# KMO_IO_MV7.net
KiCad netlist of a schematic drawn in EAGLE
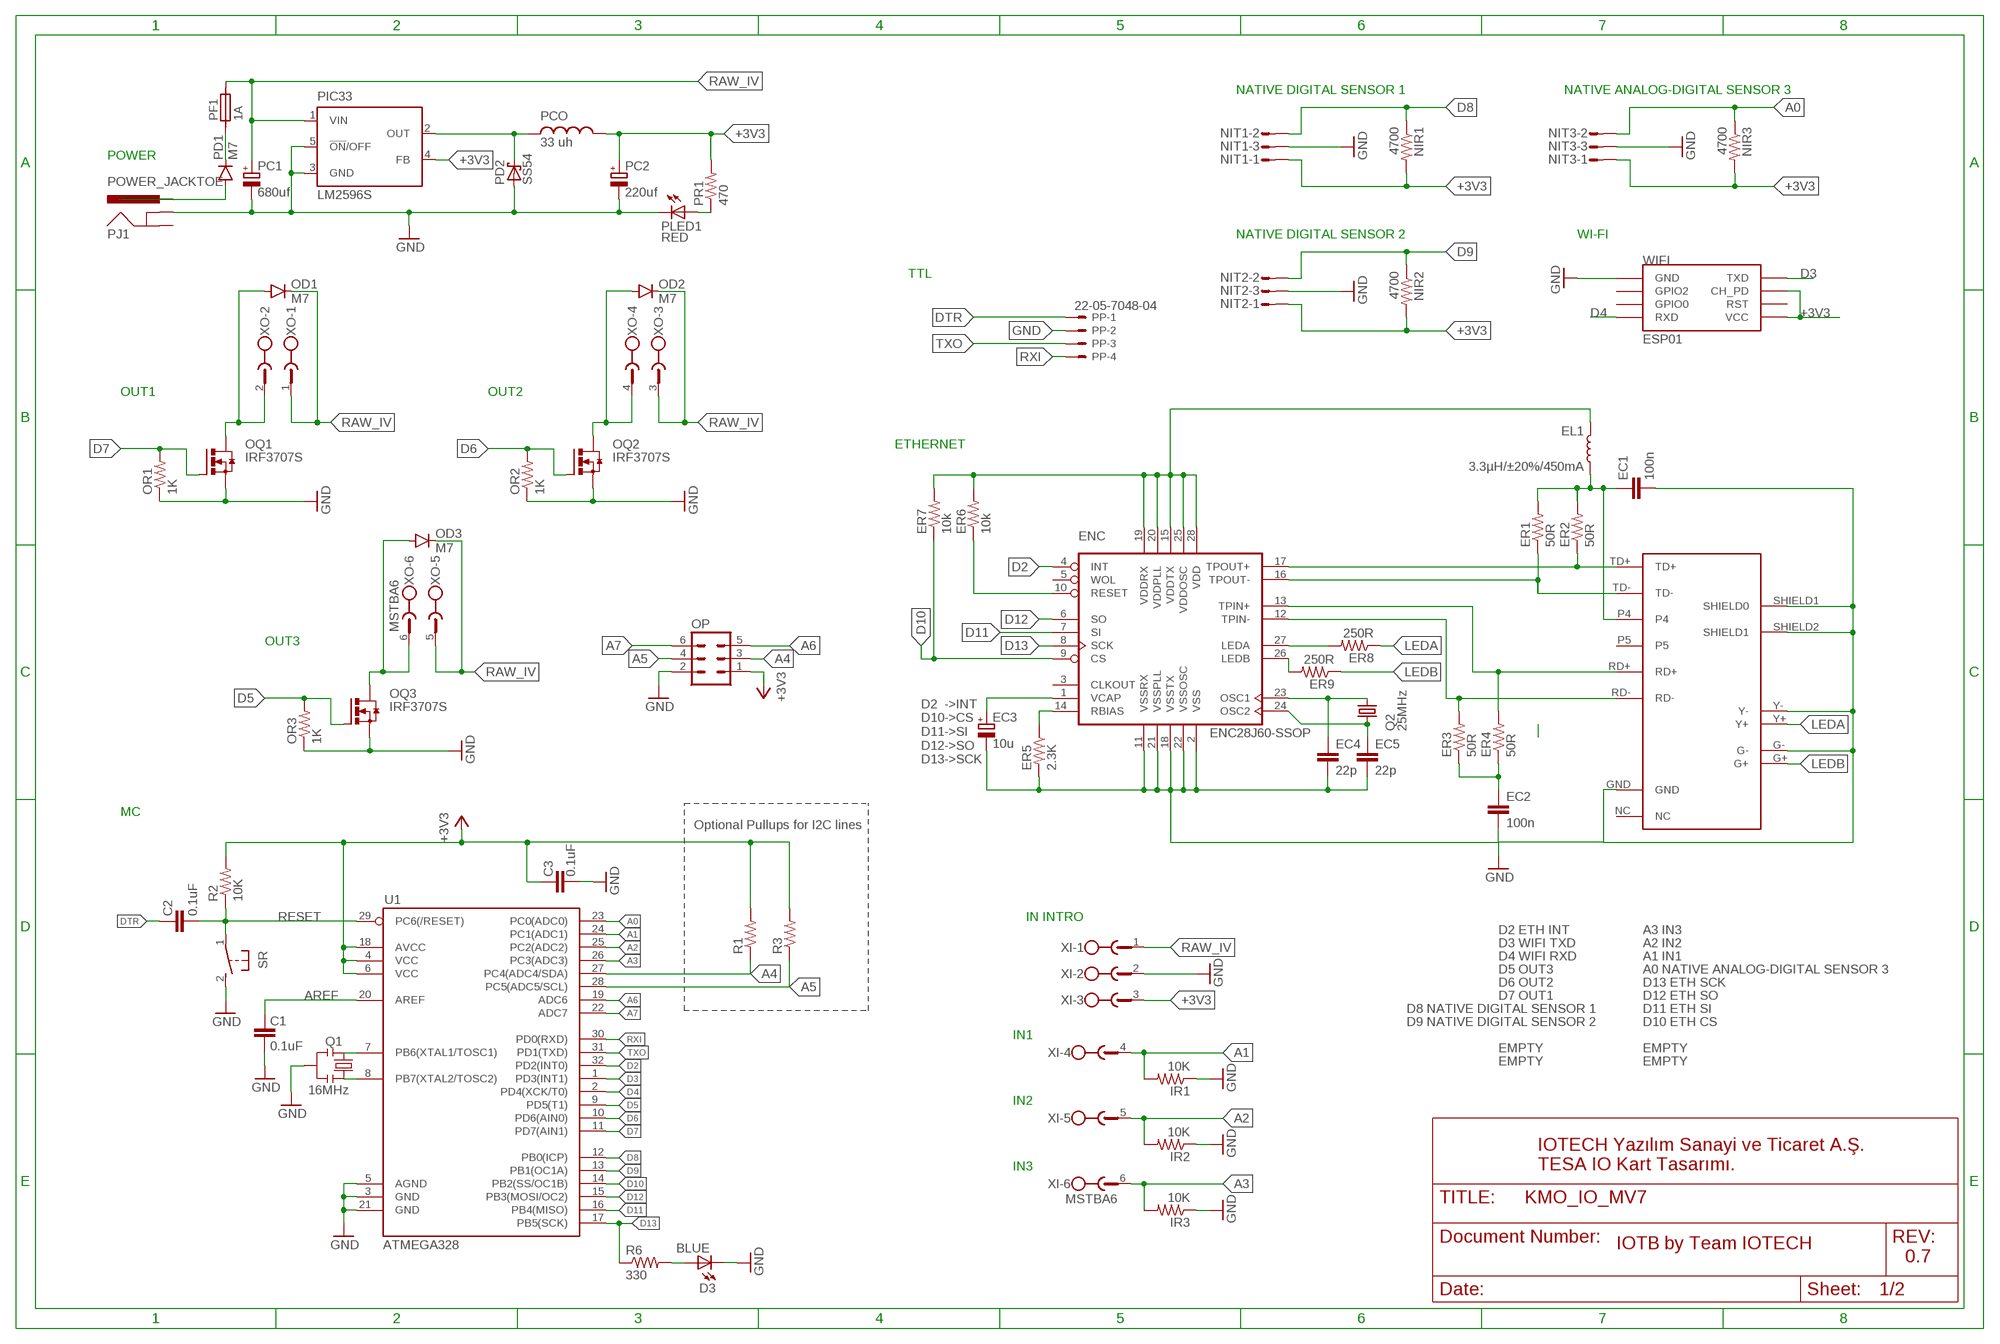
[diagram p0: schematic, sheet 1]
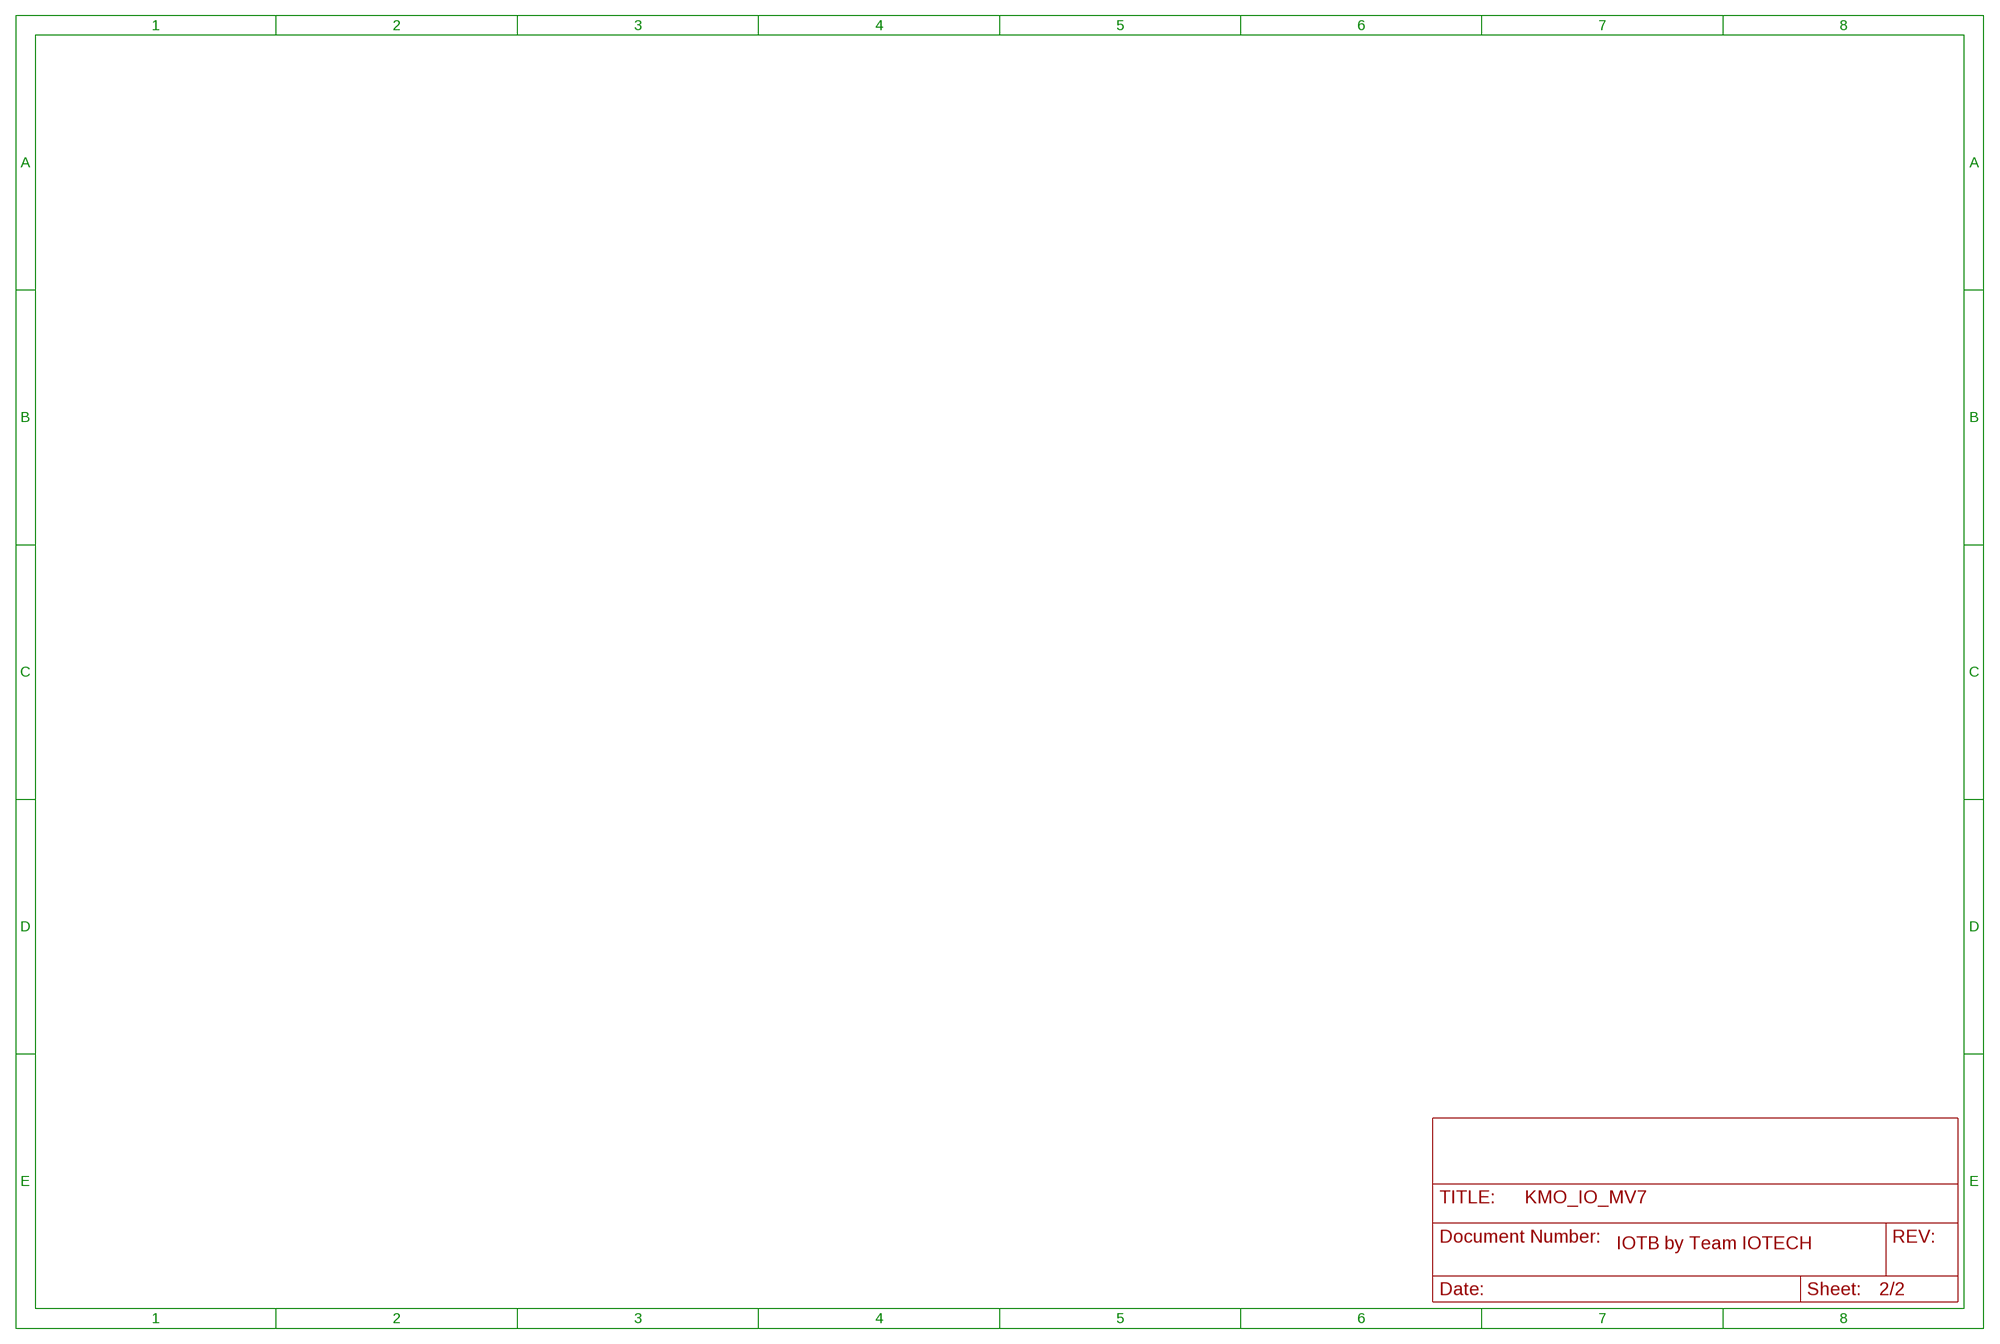
[diagram p1: schematic, sheet 2]

(export (version "E")
  (design (tool "Eeschema 10.0.6"))
  (components
    (comp (ref "C1")
      (value "0.1uF")
      (footprint "eagle-import:0805")
      (libsource (lib "eagle-import") (part "CAP0805"))
    )
    (comp (ref "C2")
      (value "0.1uF")
      (footprint "eagle-import:0805")
      (libsource (lib "eagle-import") (part "CAP0805"))
    )
    (comp (ref "C3")
      (value "0.1uF")
      (footprint "eagle-import:0805")
      (libsource (lib "eagle-import") (part "CAP0805"))
    )
    (comp (ref "D3")
      (value "BLUE")
      (footprint "eagle-import:CHIP-LED0805")
      (libsource (lib "eagle-import") (part "LEDCHIP-LED0805"))
    )
    (comp (ref "EC1")
      (value "100n")
      (footprint "eagle-import:0805")
      (libsource (lib "eagle-import") (part "CAP0805"))
    )
    (comp (ref "EC2")
      (value "100n")
      (footprint "eagle-import:0805")
      (libsource (lib "eagle-import") (part "CAP0805"))
    )
    (comp (ref "EC3")
      (value "10u")
      (footprint "eagle-import:CT3216")
      (libsource (lib "eagle-import") (part "CPOL-EUCT3216"))
    )
    (comp (ref "EC4")
      (value "22p")
      (footprint "eagle-import:0805")
      (libsource (lib "eagle-import") (part "CAP0805"))
    )
    (comp (ref "EC5")
      (value "22p")
      (footprint "eagle-import:0805")
      (libsource (lib "eagle-import") (part "CAP0805"))
    )
    (comp (ref "EL1")
      (value "3.3µH/±20%/450mA")
      (footprint "eagle-import:0805")
      (libsource (lib "eagle-import") (part "INDUCTOR-0805-3.3UH"))
    )
    (comp (ref "ENC")
      (value "ENC28J60-SSOP")
      (footprint "eagle-import:SSOP28")
      (libsource (lib "eagle-import") (part "ENC28J60-SSOP"))
    )
    (comp (ref "ER1")
      (value "50R")
      (footprint "eagle-import:0805")
      (libsource (lib "eagle-import") (part "RESISTOR0805-RES"))
    )
    (comp (ref "ER2")
      (value "50R")
      (footprint "eagle-import:0805")
      (libsource (lib "eagle-import") (part "RESISTOR0805-RES"))
    )
    (comp (ref "ER3")
      (value "50R")
      (footprint "eagle-import:0805")
      (libsource (lib "eagle-import") (part "RESISTOR0805-RES"))
    )
    (comp (ref "ER4")
      (value "50R")
      (footprint "eagle-import:0805")
      (libsource (lib "eagle-import") (part "RESISTOR0805-RES"))
    )
    (comp (ref "ER5")
      (value "2.3K")
      (footprint "eagle-import:0805")
      (libsource (lib "eagle-import") (part "RESISTOR0805-RES"))
    )
    (comp (ref "ER6")
      (value "10k")
      (footprint "eagle-import:0805")
      (libsource (lib "eagle-import") (part "RESISTOR0805-RES"))
    )
    (comp (ref "ER7")
      (value "10k")
      (footprint "eagle-import:0805")
      (libsource (lib "eagle-import") (part "RESISTOR0805-RES"))
    )
    (comp (ref "ER8")
      (value "250R")
      (footprint "eagle-import:0805")
      (libsource (lib "eagle-import") (part "RESISTOR0805-RES"))
    )
    (comp (ref "ER9")
      (value "250R")
      (footprint "eagle-import:0805")
      (libsource (lib "eagle-import") (part "RESISTOR0805-RES"))
    )
    (comp (ref "IR1")
      (value "10K")
      (footprint "eagle-import:0805")
      (libsource (lib "eagle-import") (part "RESISTOR0805-RES"))
    )
    (comp (ref "IR2")
      (value "10K")
      (footprint "eagle-import:0805")
      (libsource (lib "eagle-import") (part "RESISTOR0805-RES"))
    )
    (comp (ref "IR3")
      (value "10K")
      (footprint "eagle-import:0805")
      (libsource (lib "eagle-import") (part "RESISTOR0805-RES"))
    )
    (comp (ref "NIR1")
      (value "4700")
      (footprint "eagle-import:0805")
      (libsource (lib "eagle-import") (part "RESISTOR0805-RES"))
    )
    (comp (ref "NIR2")
      (value "4700")
      (footprint "eagle-import:0805")
      (libsource (lib "eagle-import") (part "RESISTOR0805-RES"))
    )
    (comp (ref "NIR3")
      (value "4700")
      (footprint "eagle-import:0805")
      (libsource (lib "eagle-import") (part "RESISTOR0805-RES"))
    )
    (comp (ref "NIT1")
      (value "S03P")
      (footprint "eagle-import:S03P")
      (libsource (lib "eagle-import") (part "S03P"))
    )
    (comp (ref "NIT2")
      (value "S03P")
      (footprint "eagle-import:S03P")
      (libsource (lib "eagle-import") (part "S03P"))
    )
    (comp (ref "NIT3")
      (value "S03P")
      (footprint "eagle-import:S03P")
      (libsource (lib "eagle-import") (part "S03P"))
    )
    (comp (ref "OD1")
      (value "M7")
      (footprint "eagle-import:SMA-DIODE")
      (libsource (lib "eagle-import") (part "DIODESMA"))
    )
    (comp (ref "OD2")
      (value "M7")
      (footprint "eagle-import:SMA-DIODE")
      (libsource (lib "eagle-import") (part "DIODESMA"))
    )
    (comp (ref "OD3")
      (value "M7")
      (footprint "eagle-import:SMA-DIODE")
      (libsource (lib "eagle-import") (part "DIODESMA"))
    )
    (comp (ref "OP")
      (value "MA03-2")
      (footprint "eagle-import:MA03-2")
      (libsource (lib "eagle-import") (part "MA03-2"))
    )
    (comp (ref "OQ1")
      (value "IRF3707S")
      (footprint "eagle-import:D2PACK")
      (libsource (lib "eagle-import") (part "IRF3704S"))
    )
    (comp (ref "OQ2")
      (value "IRF3707S")
      (footprint "eagle-import:D2PACK")
      (libsource (lib "eagle-import") (part "IRF3704S"))
    )
    (comp (ref "OQ3")
      (value "IRF3707S")
      (footprint "eagle-import:D2PACK")
      (libsource (lib "eagle-import") (part "IRF3704S"))
    )
    (comp (ref "OR1")
      (value "1K")
      (footprint "eagle-import:0805")
      (libsource (lib "eagle-import") (part "RESISTOR0805-RES"))
    )
    (comp (ref "OR2")
      (value "1K")
      (footprint "eagle-import:0805")
      (libsource (lib "eagle-import") (part "RESISTOR0805-RES"))
    )
    (comp (ref "OR3")
      (value "1K")
      (footprint "eagle-import:0805")
      (libsource (lib "eagle-import") (part "RESISTOR0805-RES"))
    )
    (comp (ref "PC1")
      (value "680uf")
      (footprint "eagle-import:140CLH-1010")
      (libsource (lib "eagle-import") (part "CPOL-EU140CLH-1010"))
    )
    (comp (ref "PC2")
      (value "220uf")
      (footprint "eagle-import:140CLH-1010")
      (libsource (lib "eagle-import") (part "CPOL-EU140CLH-1010"))
    )
    (comp (ref "PCO")
      (value "33 uh")
      (footprint "eagle-import:MSS1260")
      (libsource (lib "eagle-import") (part "MSS1260"))
    )
    (comp (ref "PD1")
      (value "M7")
      (footprint "eagle-import:SMA-DIODE")
      (libsource (lib "eagle-import") (part "DIODESMA"))
    )
    (comp (ref "PD2")
      (value "SS54")
      (footprint "eagle-import:SMB")
      (libsource (lib "eagle-import") (part "SCHOTTKY-DIODESMD"))
    )
    (comp (ref "PF1")
      (value "1A")
      (footprint "eagle-import:1820")
      (libsource (lib "eagle-import") (part "SIBA194600"))
    )
    (comp (ref "PIC33")
      (value "LM2596S")
      (footprint "eagle-import:TO263-5")
      (fields (field (name "MF") "NATIONAL SEMICONDUCTOR") (field (name "MPN") "LM2596S-ADJ/NOPB"))
      (libsource (lib "eagle-import") (part "LM2596S"))
    )
    (comp (ref "PJ1")
      (value "POWER_JACKTOE")
      (footprint "eagle-import:POWER_JACK_SMD_OVERPASTE_TOE")
      (libsource (lib "eagle-import") (part "POWER_JACKTOE"))
    )
    (comp (ref "PLED1")
      (value "RED")
      (footprint "eagle-import:CHIP-LED0805")
      (libsource (lib "eagle-import") (part "LEDCHIP-LED0805"))
    )
    (comp (ref "PP")
      (value "22-05-7048-04")
      (footprint "eagle-import:7395-04")
      (fields (field (name "MF") "MOLEX"))
      (libsource (lib "eagle-import") (part "22-?-0405-7048"))
    )
    (comp (ref "PR1")
      (value "470")
      (footprint "eagle-import:0805")
      (libsource (lib "eagle-import") (part "RESISTOR0805-RES"))
    )
    (comp (ref "Q1")
      (value "16MHz")
      (footprint "eagle-import:RESONATOR-SMD-1_1")
      (libsource (lib "eagle-import") (part "RESONATOR1{colon}1"))
    )
    (comp (ref "Q2")
      (value "25MHz")
      (footprint "eagle-import:5.0X3.2_2")
      (libsource (lib "eagle-import") (part "KX-9B"))
    )
    (comp (ref "R1")
      (value "RESISTOR0805-RES")
      (footprint "eagle-import:0805")
      (libsource (lib "eagle-import") (part "RESISTOR0805-RES"))
    )
    (comp (ref "R2")
      (value "10K")
      (footprint "eagle-import:0805")
      (libsource (lib "eagle-import") (part "RESISTOR0805-RES"))
    )
    (comp (ref "R3")
      (value "RESISTOR0805-RES")
      (footprint "eagle-import:0805")
      (libsource (lib "eagle-import") (part "RESISTOR0805-RES"))
    )
    (comp (ref "R6")
      (value "330")
      (footprint "eagle-import:0805")
      (libsource (lib "eagle-import") (part "RESISTOR0805-RES"))
    )
    (comp (ref "SR")
      (value "31-XX")
      (footprint "eagle-import:B3F-31XX")
      (fields (field (name "MPN") "B3F-3100"))
      (libsource (lib "eagle-import") (part "31-XX"))
    )
    (comp (ref "U$2")
      (value "HR911105A")
      (footprint "eagle-import:RJ45")
      (libsource (lib "eagle-import") (part "HR911105A"))
    )
    (comp (ref "U1")
      (value "ATMEGA328")
      (footprint "eagle-import:TQFP32-08")
      (libsource (lib "eagle-import") (part "ATMEGA168"))
    )
    (comp (ref "WIFI")
      (value "ESP01")
      (footprint "eagle-import:ESP01")
      (libsource (lib "eagle-import") (part "ESP01"))
    )
    (comp (ref "XI")
      (value "MSTBA6")
      (footprint "eagle-import:MSTBA6")
      (fields (field (name "MF") "FARNELL") (field (name "MPN") "1757284"))
      (libsource (lib "eagle-import") (part "MSTBA6"))
    )
    (comp (ref "XO")
      (value "MSTBA6")
      (footprint "eagle-import:MSTBA6")
      (fields (field (name "MF") "FARNELL") (field (name "MPN") "1757284"))
      (libsource (lib "eagle-import") (part "MSTBA6"))
    )
  )
  (nets
    (net (code "1") (name "+3V3") (class "Default")
      (node (ref "C3") (pin "2") (pinfunction "2_2") (pintype "passive"))
      (node (ref "EL1") (pin "1") (pinfunction "1_1") (pintype "passive"))
      (node (ref "ENC") (pin "15") (pinfunction "VDDTX_15") (pintype "power_in"))
      (node (ref "ENC") (pin "19") (pinfunction "VDDRX_19") (pintype "power_in"))
      (node (ref "ENC") (pin "20") (pinfunction "VDDPLL_20") (pintype "power_in"))
      (node (ref "ENC") (pin "25") (pinfunction "VDDOSC_25") (pintype "power_in"))
      (node (ref "ENC") (pin "28") (pinfunction "VDD_28") (pintype "power_in"))
      (node (ref "ER6") (pin "2") (pinfunction "2_2") (pintype "passive"))
      (node (ref "ER7") (pin "2") (pinfunction "2_2") (pintype "passive"))
      (node (ref "NIR1") (pin "2") (pinfunction "2_2") (pintype "passive"))
      (node (ref "NIR2") (pin "2") (pinfunction "2_2") (pintype "passive"))
      (node (ref "NIR3") (pin "2") (pinfunction "2_2") (pintype "passive"))
      (node (ref "NIT1") (pin "1") (pinfunction "S_1") (pintype "passive"))
      (node (ref "NIT2") (pin "1") (pinfunction "S_1") (pintype "passive"))
      (node (ref "NIT3") (pin "1") (pinfunction "S_1") (pintype "passive"))
      (node (ref "OP") (pin "1") (pinfunction "1_1") (pintype "passive"))
      (node (ref "PC2") (pin "+") (pinfunction "+_+") (pintype "passive"))
      (node (ref "PCO") (pin "P$1") (pinfunction "P$1_P$1") (pintype "passive"))
      (node (ref "PIC33") (pin "4") (pinfunction "FB_4") (pintype "input"))
      (node (ref "PR1") (pin "2") (pinfunction "2_2") (pintype "passive"))
      (node (ref "R1") (pin "2") (pinfunction "2_2") (pintype "passive"))
      (node (ref "R2") (pin "2") (pinfunction "2_2") (pintype "passive"))
      (node (ref "R3") (pin "2") (pinfunction "2_2") (pintype "passive"))
      (node (ref "U1") (pin "18") (pinfunction "AVCC_18") (pintype "bidirectional"))
      (node (ref "U1") (pin "4") (pinfunction "VCC_4") (pintype "bidirectional"))
      (node (ref "U1") (pin "6") (pinfunction "VCC_6") (pintype "bidirectional"))
      (node (ref "WIFI") (pin "CH_PD") (pinfunction "CH_PD_CH_PD") (pintype "bidirectional"))
      (node (ref "WIFI") (pin "VCC") (pinfunction "VCC_VCC") (pintype "bidirectional"))
      (node (ref "XI") (pin "3") (pinfunction "1_3") (pintype "passive"))
    )
    (net (code "2") (name "A0") (class "Default")
      (node (ref "NIR3") (pin "1") (pinfunction "1_1") (pintype "passive"))
      (node (ref "NIT3") (pin "2") (pinfunction "S_2") (pintype "passive"))
      (node (ref "U1") (pin "23") (pinfunction "PC0(ADC0)_23") (pintype "bidirectional"))
    )
    (net (code "3") (name "A1") (class "Default")
      (node (ref "IR1") (pin "2") (pinfunction "2_2") (pintype "passive"))
      (node (ref "U1") (pin "24") (pinfunction "PC1(ADC1)_24") (pintype "bidirectional"))
      (node (ref "XI") (pin "4") (pinfunction "1_4") (pintype "passive"))
    )
    (net (code "4") (name "A2") (class "Default")
      (node (ref "IR2") (pin "2") (pinfunction "2_2") (pintype "passive"))
      (node (ref "U1") (pin "25") (pinfunction "PC2(ADC2)_25") (pintype "bidirectional"))
      (node (ref "XI") (pin "5") (pinfunction "1_5") (pintype "passive"))
    )
    (net (code "5") (name "A3") (class "Default")
      (node (ref "IR3") (pin "2") (pinfunction "2_2") (pintype "passive"))
      (node (ref "U1") (pin "26") (pinfunction "PC3(ADC3)_26") (pintype "bidirectional"))
      (node (ref "XI") (pin "6") (pinfunction "1_6") (pintype "passive"))
    )
    (net (code "6") (name "A4") (class "Default")
      (node (ref "OP") (pin "3") (pinfunction "3_3") (pintype "passive"))
      (node (ref "R1") (pin "1") (pinfunction "1_1") (pintype "passive"))
      (node (ref "U1") (pin "27") (pinfunction "PC4(ADC4/SDA)_27") (pintype "bidirectional"))
    )
    (net (code "7") (name "A5") (class "Default")
      (node (ref "OP") (pin "4") (pinfunction "4_4") (pintype "passive"))
      (node (ref "R3") (pin "1") (pinfunction "1_1") (pintype "passive"))
      (node (ref "U1") (pin "28") (pinfunction "PC5(ADC5/SCL)_28") (pintype "bidirectional"))
    )
    (net (code "8") (name "A6") (class "Default")
      (node (ref "OP") (pin "5") (pinfunction "5_5") (pintype "passive"))
      (node (ref "U1") (pin "19") (pinfunction "ADC6_19") (pintype "bidirectional"))
    )
    (net (code "9") (name "A7") (class "Default")
      (node (ref "OP") (pin "6") (pinfunction "6_6") (pintype "passive"))
      (node (ref "U1") (pin "22") (pinfunction "ADC7_22") (pintype "bidirectional"))
    )
    (net (code "10") (name "AREF") (class "Default")
      (node (ref "C1") (pin "2") (pinfunction "2_2") (pintype "passive"))
      (node (ref "U1") (pin "20") (pinfunction "AREF_20") (pintype "bidirectional"))
    )
    (net (code "11") (name "D2") (class "Default")
      (node (ref "ENC") (pin "4") (pinfunction "INT_4") (pintype "output"))
      (node (ref "U1") (pin "32") (pinfunction "PD2(INT0)_32") (pintype "bidirectional"))
    )
    (net (code "12") (name "D3") (class "Default")
      (node (ref "U1") (pin "1") (pinfunction "PD3(INT1)_1") (pintype "bidirectional"))
      (node (ref "WIFI") (pin "TX") (pinfunction "TXD_TX") (pintype "bidirectional"))
    )
    (net (code "13") (name "D4") (class "Default")
      (node (ref "U1") (pin "2") (pinfunction "PD4(XCK/T0)_2") (pintype "bidirectional"))
      (node (ref "WIFI") (pin "RX") (pinfunction "RXD_RX") (pintype "bidirectional"))
    )
    (net (code "14") (name "D5") (class "Default")
      (node (ref "OQ3") (pin "1") (pinfunction "G_1") (pintype "passive"))
      (node (ref "OR3") (pin "2") (pinfunction "2_2") (pintype "passive"))
      (node (ref "U1") (pin "9") (pinfunction "PD5(T1)_9") (pintype "bidirectional"))
    )
    (net (code "15") (name "D6") (class "Default")
      (node (ref "OQ2") (pin "1") (pinfunction "G_1") (pintype "passive"))
      (node (ref "OR2") (pin "2") (pinfunction "2_2") (pintype "passive"))
      (node (ref "U1") (pin "10") (pinfunction "PD6(AIN0)_10") (pintype "bidirectional"))
    )
    (net (code "16") (name "D7") (class "Default")
      (node (ref "OQ1") (pin "1") (pinfunction "G_1") (pintype "passive"))
      (node (ref "OR1") (pin "2") (pinfunction "2_2") (pintype "passive"))
      (node (ref "U1") (pin "11") (pinfunction "PD7(AIN1)_11") (pintype "bidirectional"))
    )
    (net (code "17") (name "D8") (class "Default")
      (node (ref "NIR1") (pin "1") (pinfunction "1_1") (pintype "passive"))
      (node (ref "NIT1") (pin "2") (pinfunction "S_2") (pintype "passive"))
      (node (ref "U1") (pin "12") (pinfunction "PB0(ICP)_12") (pintype "bidirectional"))
    )
    (net (code "18") (name "D9") (class "Default")
      (node (ref "NIR2") (pin "1") (pinfunction "1_1") (pintype "passive"))
      (node (ref "NIT2") (pin "2") (pinfunction "S_2") (pintype "passive"))
      (node (ref "U1") (pin "13") (pinfunction "PB1(OC1A)_13") (pintype "bidirectional"))
    )
    (net (code "19") (name "D10") (class "Default")
      (node (ref "ENC") (pin "9") (pinfunction "CS_9") (pintype "input"))
      (node (ref "ER7") (pin "1") (pinfunction "1_1") (pintype "passive"))
      (node (ref "U1") (pin "14") (pinfunction "PB2(SS/OC1B)_14") (pintype "bidirectional"))
    )
    (net (code "20") (name "D11") (class "Default")
      (node (ref "ENC") (pin "7") (pinfunction "SI_7") (pintype "input"))
      (node (ref "U1") (pin "16") (pinfunction "PB4(MISO)_16") (pintype "bidirectional"))
    )
    (net (code "21") (name "D12") (class "Default")
      (node (ref "ENC") (pin "6") (pinfunction "SO_6") (pintype "output"))
      (node (ref "U1") (pin "15") (pinfunction "PB3(MOSI/OC2)_15") (pintype "bidirectional"))
    )
    (net (code "22") (name "D13") (class "Default")
      (node (ref "ENC") (pin "8") (pinfunction "SCK_8") (pintype "input"))
      (node (ref "R6") (pin "1") (pinfunction "1_1") (pintype "passive"))
      (node (ref "U1") (pin "17") (pinfunction "PB5(SCK)_17") (pintype "bidirectional"))
    )
    (net (code "23") (name "DTR") (class "Default")
      (node (ref "C2") (pin "2") (pinfunction "2_2") (pintype "passive"))
      (node (ref "PP") (pin "1") (pinfunction "S_1") (pintype "passive"))
    )
    (net (code "24") (name "GND") (class "Default")
      (node (ref "C1") (pin "1") (pinfunction "1_1") (pintype "passive"))
      (node (ref "C3") (pin "1") (pinfunction "1_1") (pintype "passive"))
      (node (ref "D3") (pin "C") (pinfunction "C_C") (pintype "passive"))
      (node (ref "EC1") (pin "2") (pinfunction "2_2") (pintype "passive"))
      (node (ref "EC2") (pin "2") (pinfunction "2_2") (pintype "passive"))
      (node (ref "EC3") (pin "-") (pinfunction "-_-") (pintype "passive"))
      (node (ref "EC4") (pin "2") (pinfunction "2_2") (pintype "passive"))
      (node (ref "EC5") (pin "2") (pinfunction "2_2") (pintype "passive"))
      (node (ref "ENC") (pin "11") (pinfunction "VSSRX_11") (pintype "power_in"))
      (node (ref "ENC") (pin "18") (pinfunction "VSSTX_18") (pintype "power_in"))
      (node (ref "ENC") (pin "2") (pinfunction "VSS_2") (pintype "power_in"))
      (node (ref "ENC") (pin "21") (pinfunction "VSSPLL_21") (pintype "power_in"))
      (node (ref "ENC") (pin "22") (pinfunction "VSSOSC_22") (pintype "power_in"))
      (node (ref "ER5") (pin "2") (pinfunction "2_2") (pintype "passive"))
      (node (ref "IR1") (pin "1") (pinfunction "1_1") (pintype "passive"))
      (node (ref "IR2") (pin "1") (pinfunction "1_1") (pintype "passive"))
      (node (ref "IR3") (pin "1") (pinfunction "1_1") (pintype "passive"))
      (node (ref "NIT1") (pin "3") (pinfunction "S_3") (pintype "passive"))
      (node (ref "NIT2") (pin "3") (pinfunction "S_3") (pintype "passive"))
      (node (ref "NIT3") (pin "3") (pinfunction "S_3") (pintype "passive"))
      (node (ref "OP") (pin "2") (pinfunction "2_2") (pintype "passive"))
      (node (ref "OQ1") (pin "3") (pinfunction "S_3") (pintype "passive"))
      (node (ref "OQ2") (pin "3") (pinfunction "S_3") (pintype "passive"))
      (node (ref "OQ3") (pin "3") (pinfunction "S_3") (pintype "passive"))
      (node (ref "OR1") (pin "1") (pinfunction "1_1") (pintype "passive"))
      (node (ref "OR2") (pin "1") (pinfunction "1_1") (pintype "passive"))
      (node (ref "OR3") (pin "1") (pinfunction "1_1") (pintype "passive"))
      (node (ref "PC1") (pin "-") (pinfunction "-_-") (pintype "passive"))
      (node (ref "PC2") (pin "-") (pinfunction "-_-") (pintype "passive"))
      (node (ref "PD2") (pin "A") (pinfunction "A_A") (pintype "passive"))
      (node (ref "PIC33") (pin "3") (pinfunction "GND_3") (pintype "power_in"))
      (node (ref "PIC33") (pin "5") (pinfunction "~{ON}/OFF_5") (pintype "input"))
      (node (ref "PJ1") (pin "GND") (pinfunction "GNDBREAK_GND") (pintype "bidirectional"))
      (node (ref "PLED1") (pin "C") (pinfunction "C_C") (pintype "passive"))
      (node (ref "PP") (pin "2") (pinfunction "S_2") (pintype "passive"))
      (node (ref "Q1") (pin "2") (pinfunction "2_2") (pintype "passive"))
      (node (ref "SR") (pin "2") (pinfunction "S_2") (pintype "passive"))
      (node (ref "U$2") (pin "G-") (pinfunction "G-_G-") (pintype "bidirectional"))
      (node (ref "U$2") (pin "GND") (pinfunction "GND_GND") (pintype "bidirectional"))
      (node (ref "U$2") (pin "SHIELD1") (pinfunction "SHIELD0_SHIELD1") (pintype "bidirectional"))
      (node (ref "U$2") (pin "SHIELD2") (pinfunction "SHIELD1_SHIELD2") (pintype "bidirectional"))
      (node (ref "U$2") (pin "Y-") (pinfunction "Y-_Y-") (pintype "bidirectional"))
      (node (ref "U1") (pin "21") (pinfunction "GND_21") (pintype "bidirectional"))
      (node (ref "U1") (pin "3") (pinfunction "GND_3") (pintype "bidirectional"))
      (node (ref "U1") (pin "5") (pinfunction "AGND_5") (pintype "bidirectional"))
      (node (ref "WIFI") (pin "GND") (pinfunction "GND_GND") (pintype "bidirectional"))
      (node (ref "XI") (pin "2") (pinfunction "1_2") (pintype "passive"))
    )
    (net (code "25") (name "LEDA") (class "Default")
      (node (ref "ER8") (pin "1") (pinfunction "1_1") (pintype "passive"))
      (node (ref "U$2") (pin "Y+") (pinfunction "Y+_Y+") (pintype "bidirectional"))
    )
    (net (code "26") (name "LEDB") (class "Default")
      (node (ref "ER9") (pin "1") (pinfunction "1_1") (pintype "passive"))
      (node (ref "U$2") (pin "G+") (pinfunction "G+_G+") (pintype "bidirectional"))
    )
    (net (code "27") (name "Net-(D3-PadA)") (class "Default")
      (node (ref "D3") (pin "A") (pinfunction "A_A") (pintype "passive"))
      (node (ref "R6") (pin "2") (pinfunction "2_2") (pintype "passive"))
    )
    (net (code "28") (name "Net-(EC1-Pad1)") (class "Default")
      (node (ref "EC1") (pin "1") (pinfunction "1_1") (pintype "passive"))
      (node (ref "EL1") (pin "2") (pinfunction "2_2") (pintype "passive"))
      (node (ref "ER1") (pin "2") (pinfunction "2_2") (pintype "passive"))
      (node (ref "ER2") (pin "2") (pinfunction "2_2") (pintype "passive"))
      (node (ref "U$2") (pin "P4") (pinfunction "P4_P4") (pintype "bidirectional"))
    )
    (net (code "29") (name "Net-(EC2-Pad1)") (class "Default")
      (node (ref "EC2") (pin "1") (pinfunction "1_1") (pintype "passive"))
      (node (ref "ER3") (pin "1") (pinfunction "1_1") (pintype "passive"))
      (node (ref "ER4") (pin "1") (pinfunction "1_1") (pintype "passive"))
    )
    (net (code "30") (name "Net-(ENC-LEDA)") (class "Default")
      (node (ref "ENC") (pin "27") (pinfunction "LEDA_27") (pintype "output"))
      (node (ref "ER8") (pin "2") (pinfunction "2_2") (pintype "passive"))
    )
    (net (code "31") (name "Net-(ENC-LEDB)") (class "Default")
      (node (ref "ENC") (pin "26") (pinfunction "LEDB_26") (pintype "output"))
      (node (ref "ER9") (pin "2") (pinfunction "2_2") (pintype "passive"))
    )
    (net (code "32") (name "Net-(ENC-OSC1)") (class "Default")
      (node (ref "EC4") (pin "1") (pinfunction "1_1") (pintype "passive"))
      (node (ref "ENC") (pin "23") (pinfunction "OSC1_23") (pintype "input"))
      (node (ref "Q2") (pin "2") (pinfunction "2_2") (pintype "passive"))
    )
    (net (code "33") (name "Net-(ENC-OSC2)") (class "Default")
      (node (ref "EC5") (pin "1") (pinfunction "1_1") (pintype "passive"))
      (node (ref "ENC") (pin "24") (pinfunction "OSC2_24") (pintype "output"))
      (node (ref "Q2") (pin "1") (pinfunction "1_1") (pintype "passive"))
    )
    (net (code "34") (name "Net-(ENC-RBIAS)") (class "Default")
      (node (ref "ENC") (pin "14") (pinfunction "RBIAS_14") (pintype "passive"))
      (node (ref "ER5") (pin "1") (pinfunction "1_1") (pintype "passive"))
    )
    (net (code "35") (name "Net-(ENC-RESET)") (class "Default")
      (node (ref "ENC") (pin "10") (pinfunction "RESET_10") (pintype "input"))
      (node (ref "ER6") (pin "1") (pinfunction "1_1") (pintype "passive"))
    )
    (net (code "36") (name "Net-(ENC-TPIN+)") (class "Default")
      (node (ref "ENC") (pin "13") (pinfunction "TPIN+_13") (pintype "input"))
      (node (ref "ER4") (pin "2") (pinfunction "2_2") (pintype "passive"))
      (node (ref "U$2") (pin "RD+") (pinfunction "RD+_RD+") (pintype "bidirectional"))
    )
    (net (code "37") (name "Net-(ENC-TPIN-)") (class "Default")
      (node (ref "ENC") (pin "12") (pinfunction "TPIN-_12") (pintype "input"))
      (node (ref "ER3") (pin "2") (pinfunction "2_2") (pintype "passive"))
      (node (ref "U$2") (pin "RD-") (pinfunction "RD-_RD-") (pintype "bidirectional"))
    )
    (net (code "38") (name "Net-(ENC-TPOUT+)") (class "Default")
      (node (ref "ENC") (pin "17") (pinfunction "TPOUT+_17") (pintype "output"))
      (node (ref "ER2") (pin "1") (pinfunction "1_1") (pintype "passive"))
      (node (ref "U$2") (pin "TD+") (pinfunction "TD+_TD+") (pintype "bidirectional"))
    )
    (net (code "39") (name "Net-(ENC-TPOUT-)") (class "Default")
      (node (ref "ENC") (pin "16") (pinfunction "TPOUT-_16") (pintype "output"))
      (node (ref "ER1") (pin "1") (pinfunction "1_1") (pintype "passive"))
      (node (ref "U$2") (pin "TD-") (pinfunction "TD-_TD-") (pintype "bidirectional"))
    )
    (net (code "40") (name "Net-(ENC-VCAP)") (class "Default")
      (node (ref "EC3") (pin "+") (pinfunction "+_+") (pintype "passive"))
      (node (ref "ENC") (pin "1") (pinfunction "VCAP_1") (pintype "power_in"))
    )
    (net (code "41") (name "Net-(OQ1-D)") (class "Default")
      (node (ref "OD1") (pin "A") (pinfunction "A_A") (pintype "passive"))
      (node (ref "OQ1") (pin "2") (pinfunction "D_2") (pintype "passive"))
      (node (ref "XO") (pin "2") (pinfunction "1_2") (pintype "passive"))
    )
    (net (code "42") (name "Net-(OQ2-D)") (class "Default")
      (node (ref "OD2") (pin "A") (pinfunction "A_A") (pintype "passive"))
      (node (ref "OQ2") (pin "2") (pinfunction "D_2") (pintype "passive"))
      (node (ref "XO") (pin "4") (pinfunction "1_4") (pintype "passive"))
    )
    (net (code "43") (name "Net-(OQ3-D)") (class "Default")
      (node (ref "OD3") (pin "A") (pinfunction "A_A") (pintype "passive"))
      (node (ref "OQ3") (pin "2") (pinfunction "D_2") (pintype "passive"))
      (node (ref "XO") (pin "6") (pinfunction "1_6") (pintype "passive"))
    )
    (net (code "44") (name "Net-(PD1-PadC)") (class "Default")
      (node (ref "PD1") (pin "C") (pinfunction "C_C") (pintype "passive"))
      (node (ref "PF1") (pin "1") (pinfunction "1_1") (pintype "passive"))
    )
    (net (code "45") (name "Net-(PIC33-OUT)") (class "Default")
      (node (ref "PCO") (pin "P$2") (pinfunction "P$2_P$2") (pintype "passive"))
      (node (ref "PD2") (pin "C") (pinfunction "C_C") (pintype "passive"))
      (node (ref "PIC33") (pin "2") (pinfunction "OUT_2") (pintype "output"))
    )
    (net (code "46") (name "Net-(PJ1-PWR)") (class "Default")
      (node (ref "PD1") (pin "A") (pinfunction "A_A") (pintype "passive"))
      (node (ref "PJ1") (pin "VIN0") (pinfunction "PWR_VIN0") (pintype "bidirectional"))
    )
    (net (code "47") (name "Net-(PLED1-PadA)") (class "Default")
      (node (ref "PLED1") (pin "A") (pinfunction "A_A") (pintype "passive"))
      (node (ref "PR1") (pin "1") (pinfunction "1_1") (pintype "passive"))
    )
    (net (code "48") (name "Net-(U1-PB6(XTAL1{slash}TOSC1))") (class "Default")
      (node (ref "Q1") (pin "1") (pinfunction "1_1") (pintype "passive"))
      (node (ref "U1") (pin "7") (pinfunction "PB6(XTAL1/TOSC1)_7") (pintype "bidirectional"))
    )
    (net (code "49") (name "Net-(U1-PB7(XTAL2{slash}TOSC2))") (class "Default")
      (node (ref "Q1") (pin "3") (pinfunction "3_3") (pintype "passive"))
      (node (ref "U1") (pin "8") (pinfunction "PB7(XTAL2/TOSC2)_8") (pintype "bidirectional"))
    )
    (net (code "50") (name "RAW_IV") (class "Default")
      (node (ref "OD1") (pin "C") (pinfunction "C_C") (pintype "passive"))
      (node (ref "OD2") (pin "C") (pinfunction "C_C") (pintype "passive"))
      (node (ref "OD3") (pin "C") (pinfunction "C_C") (pintype "passive"))
      (node (ref "PC1") (pin "+") (pinfunction "+_+") (pintype "passive"))
      (node (ref "PF1") (pin "2") (pinfunction "2_2") (pintype "passive"))
      (node (ref "PIC33") (pin "1") (pinfunction "VIN_1") (pintype "input"))
      (node (ref "XI") (pin "1") (pinfunction "1_1") (pintype "passive"))
      (node (ref "XO") (pin "1") (pinfunction "1_1") (pintype "passive"))
      (node (ref "XO") (pin "3") (pinfunction "1_3") (pintype "passive"))
      (node (ref "XO") (pin "5") (pinfunction "1_5") (pintype "passive"))
    )
    (net (code "51") (name "RESET") (class "Default")
      (node (ref "C2") (pin "1") (pinfunction "1_1") (pintype "passive"))
      (node (ref "R2") (pin "1") (pinfunction "1_1") (pintype "passive"))
      (node (ref "SR") (pin "1") (pinfunction "P_1") (pintype "passive"))
      (node (ref "U1") (pin "29") (pinfunction "PC6(/RESET)_29") (pintype "bidirectional"))
    )
    (net (code "52") (name "RXI") (class "Default")
      (node (ref "PP") (pin "4") (pinfunction "S_4") (pintype "passive"))
      (node (ref "U1") (pin "30") (pinfunction "PD0(RXD)_30") (pintype "bidirectional"))
    )
    (net (code "53") (name "TXO") (class "Default")
      (node (ref "PP") (pin "3") (pinfunction "S_3") (pintype "passive"))
      (node (ref "U1") (pin "31") (pinfunction "PD1(TXD)_31") (pintype "bidirectional"))
    )
    (net (code "54") (name "unconnected-(ENC-CLKOUT-Pad3)") (class "Default")
      (node (ref "ENC") (pin "3") (pinfunction "CLKOUT_3") (pintype "output"))
    )
    (net (code "55") (name "unconnected-(ENC-WOL-Pad5)") (class "Default")
      (node (ref "ENC") (pin "5") (pinfunction "WOL_5") (pintype "output"))
    )
    (net (code "56") (name "unconnected-(PJ1-GND-PadP$4)") (class "Default")
      (node (ref "PJ1") (pin "P$4") (pinfunction "GND_P$4") (pintype "bidirectional"))
    )
    (net (code "57") (name "unconnected-(U$2-PadNC)") (class "Default")
      (node (ref "U$2") (pin "NC") (pinfunction "NC_NC") (pintype "bidirectional"))
    )
    (net (code "58") (name "unconnected-(U$2-PadP5)") (class "Default")
      (node (ref "U$2") (pin "P5") (pinfunction "P5_P5") (pintype "bidirectional"))
    )
    (net (code "59") (name "unconnected-(WIFI-PadGPIO0)") (class "Default")
      (node (ref "WIFI") (pin "GPIO0") (pinfunction "GPIO0_GPIO0") (pintype "bidirectional"))
    )
    (net (code "60") (name "unconnected-(WIFI-PadGPIO2)") (class "Default")
      (node (ref "WIFI") (pin "GPIO2") (pinfunction "GPIO2_GPIO2") (pintype "bidirectional"))
    )
    (net (code "61") (name "unconnected-(WIFI-PadRST)") (class "Default")
      (node (ref "WIFI") (pin "RST") (pinfunction "RST_RST") (pintype "bidirectional"))
    )
  )
)
